# GasALIM.net
KiCad netlist of a schematic drawn in EAGLE
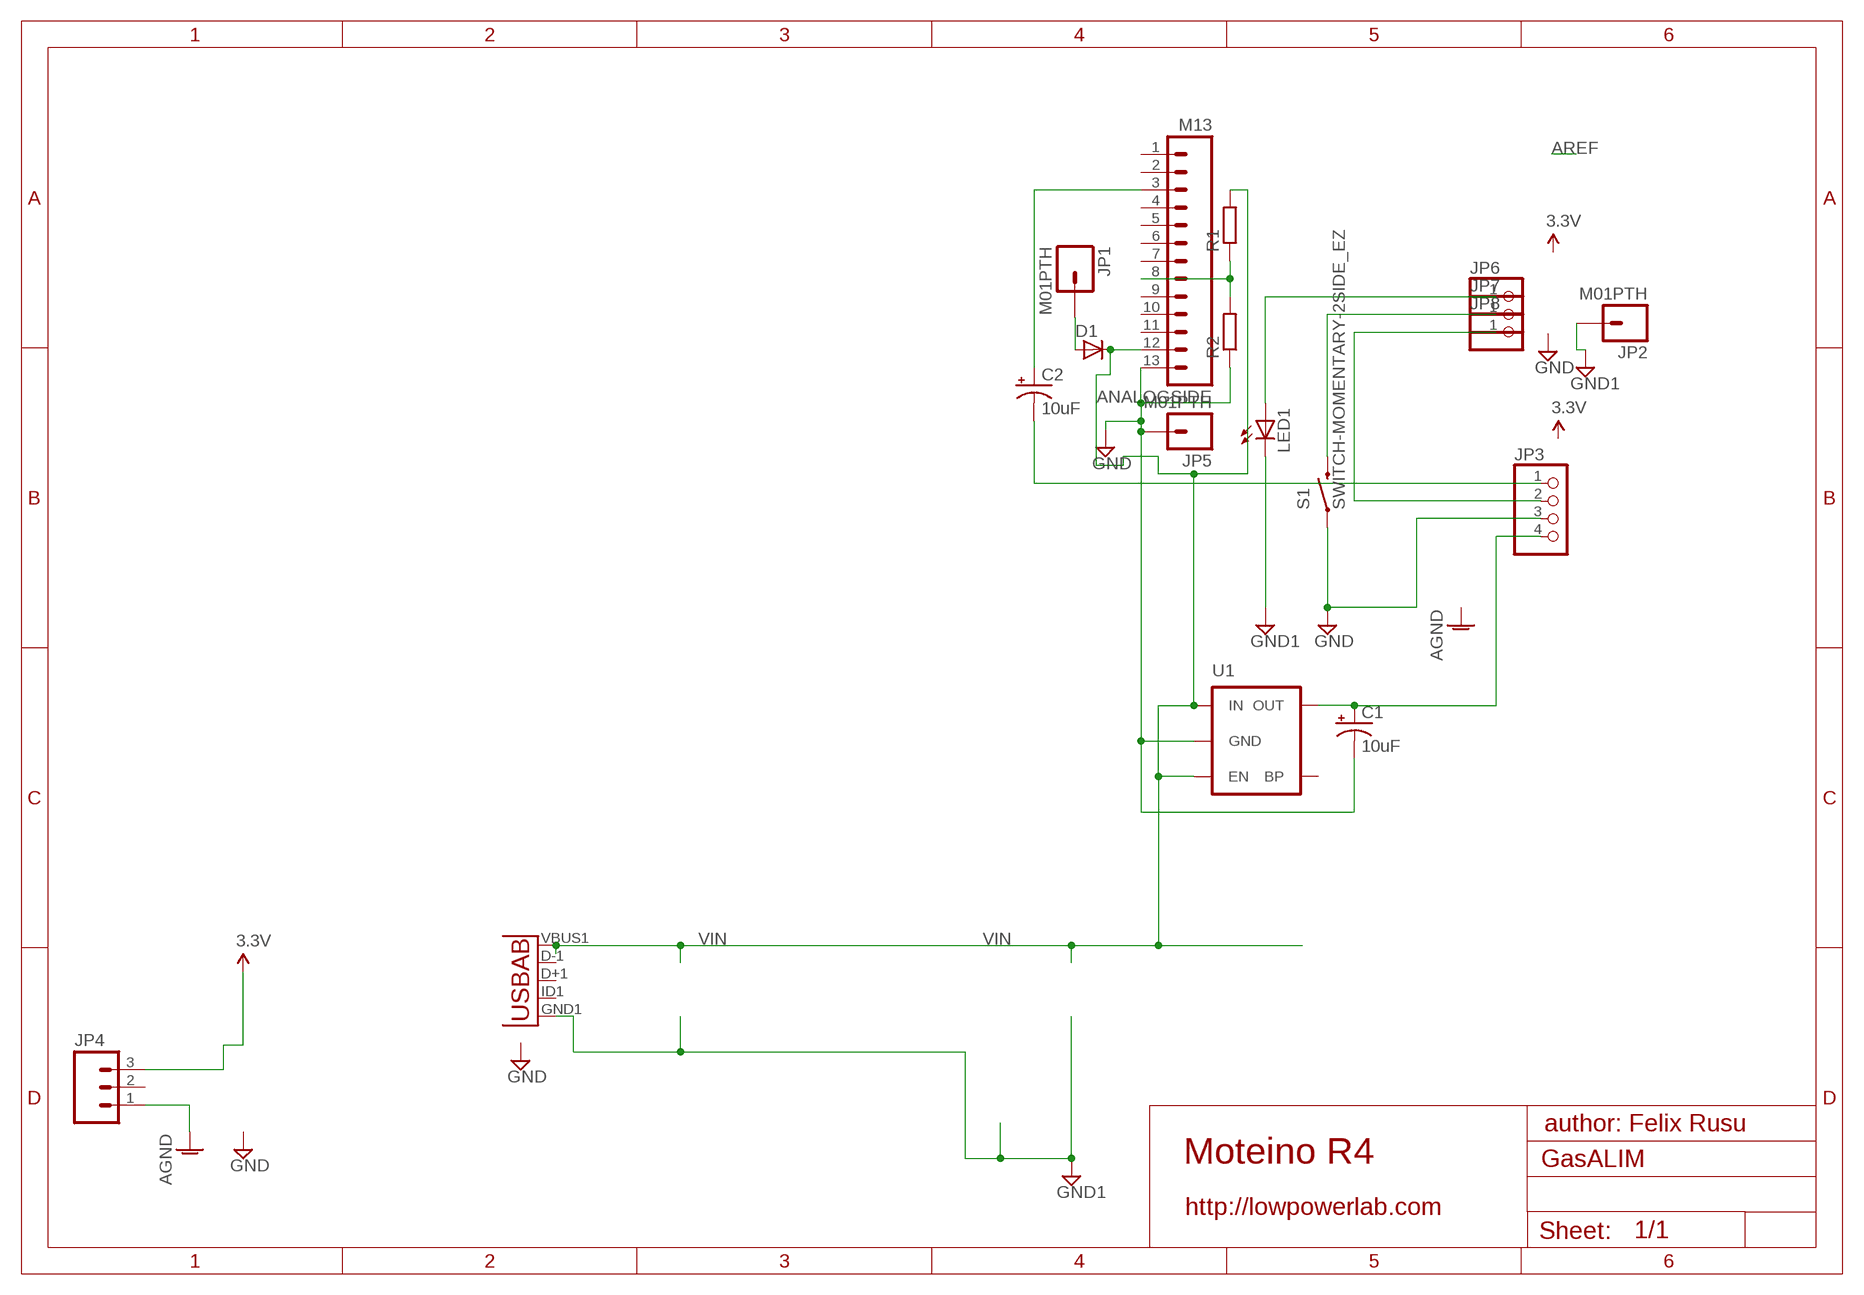
[diagram p0: schematic, sheet 1]

(export (version "E")
  (design (tool "Eeschema 10.0.6"))
  (components
    (comp (ref "ANALOGSIDE")
      (value "M13")
      (footprint "eagle-import:1X13")
      (libsource (lib "eagle-import") (part "M13"))
    )
    (comp (ref "C1")
      (value "10uF")
      (footprint "eagle-import:EIA3216")
      (libsource (lib "eagle-import") (part "10UF-16V-10%(TANT)"))
    )
    (comp (ref "C2")
      (value "10uF")
      (footprint "eagle-import:EIA3216")
      (libsource (lib "eagle-import") (part "10UF-16V-10%(TANT)"))
    )
    (comp (ref "D1")
      (value "D-MLL-34")
      (footprint "eagle-import:MELF-MLL34")
      (libsource (lib "eagle-import") (part "D-MLL-34"))
    )
    (comp (ref "JP1")
      (value "M01PTH")
      (footprint "eagle-import:1X01")
      (libsource (lib "eagle-import") (part "M01PTH"))
    )
    (comp (ref "JP2")
      (value "M01PTH")
      (footprint "eagle-import:1X01")
      (libsource (lib "eagle-import") (part "M01PTH"))
    )
    (comp (ref "JP3")
      (value "PINHD-1X4")
      (footprint "eagle-import:1X04")
      (libsource (lib "eagle-import") (part "PINHD-1X4"))
    )
    (comp (ref "JP4")
      (value "M03PTH")
      (footprint "eagle-import:1X03")
      (libsource (lib "eagle-import") (part "M03PTH"))
    )
    (comp (ref "JP5")
      (value "M01PTH")
      (footprint "eagle-import:1X01")
      (libsource (lib "eagle-import") (part "M01PTH"))
    )
    (comp (ref "JP6")
      (value "PINHD-1X1")
      (footprint "eagle-import:1X01")
      (libsource (lib "eagle-import") (part "PINHD-1X1"))
    )
    (comp (ref "JP7")
      (value "PINHD-1X1")
      (footprint "eagle-import:1X01")
      (libsource (lib "eagle-import") (part "PINHD-1X1"))
    )
    (comp (ref "JP8")
      (value "PINHD-1X1")
      (footprint "eagle-import:1X01")
      (libsource (lib "eagle-import") (part "PINHD-1X1"))
    )
    (comp (ref "JP9")
      (value "Micro USB")
      (footprint "eagle-import:USB-AB-MICRO-SMD_V03")
      (libsource (lib "eagle-import") (part "USB-ABCONN-11794"))
    )
    (comp (ref "LED1")
      (value "LED3MM")
      (footprint "eagle-import:LED3MM")
      (libsource (lib "eagle-import") (part "LED3MM"))
    )
    (comp (ref "R1")
      (value "R-EU_0204/7")
      (footprint "eagle-import:0204_7")
      (libsource (lib "eagle-import") (part "R-EU_0204/7"))
    )
    (comp (ref "R2")
      (value "R-EU_0204/7")
      (footprint "eagle-import:0204_7")
      (libsource (lib "eagle-import") (part "R-EU_0204/7"))
    )
    (comp (ref "S1")
      (value "SWITCH-MOMENTARY-2SIDE_EZ")
      (footprint "eagle-import:TACTILE-PTH-SIDEEZ")
      (libsource (lib "eagle-import") (part "SWITCH-MOMENTARY-2SIDE_EZ"))
    )
    (comp (ref "U1")
      (value "MIC52055V")
      (footprint "eagle-import:SOT23-5@1")
      (libsource (lib "eagle-import") (part "MIC52055V"))
    )
  )
  (nets
    (net (code "2") (name "/VIN") (class "Default")
      (node (ref "ANALOGSIDE") (pin "12") (pinfunction "12_12") (pintype "passive"))
      (node (ref "D1") (pin "1") (pinfunction "C_1") (pintype "passive"))
      (node (ref "JP9") (pin "VBUS1") (pinfunction "VBUS_VBUS1") (pintype "bidirectional"))
      (node (ref "R1") (pin "2") (pinfunction "2_2") (pintype "passive"))
      (node (ref "U1") (pin "1") (pinfunction "IN_1") (pintype "input"))
      (node (ref "U1") (pin "3") (pinfunction "EN_3") (pintype "input"))
    )
    (net (code "3") (name "3.3V") (class "Default")
      (node (ref "JP4") (pin "3") (pinfunction "3_3") (pintype "passive"))
    )
    (net (code "4") (name "AGND") (class "Default")
      (node (ref "JP4") (pin "1") (pinfunction "1_1") (pintype "passive"))
    )
    (net (code "5") (name "GND") (class "Default")
      (node (ref "ANALOGSIDE") (pin "13") (pinfunction "13_13") (pintype "passive"))
      (node (ref "C1") (pin "C") (pinfunction "-_C") (pintype "passive"))
      (node (ref "JP3") (pin "3") (pinfunction "3_3") (pintype "passive"))
      (node (ref "JP5") (pin "1") (pinfunction "1_1") (pintype "passive"))
      (node (ref "R2") (pin "1") (pinfunction "1_1") (pintype "passive"))
      (node (ref "S1") (pin "1") (pinfunction "1_1") (pintype "passive"))
      (node (ref "U1") (pin "2") (pinfunction "GND_2") (pintype "input"))
    )
    (net (code "6") (name "GND1") (class "Default")
      (node (ref "JP2") (pin "1") (pinfunction "1_1") (pintype "passive"))
      (node (ref "JP9") (pin "GND1") (pinfunction "GND_GND1") (pintype "bidirectional"))
      (node (ref "LED1") (pin "K") (pinfunction "C_K") (pintype "passive"))
    )
    (net (code "7") (name "Net-(ANALOGSIDE-Pad8)") (class "Default")
      (node (ref "ANALOGSIDE") (pin "8") (pinfunction "8_8") (pintype "passive"))
      (node (ref "R1") (pin "1") (pinfunction "1_1") (pintype "passive"))
      (node (ref "R2") (pin "2") (pinfunction "2_2") (pintype "passive"))
    )
    (net (code "8") (name "Net-(C1-+)") (class "Default")
      (node (ref "C1") (pin "A") (pinfunction "+_A") (pintype "passive"))
      (node (ref "JP3") (pin "4") (pinfunction "4_4") (pintype "passive"))
      (node (ref "U1") (pin "5") (pinfunction "OUT_5") (pintype "passive"))
    )
    (net (code "9") (name "Net-(C2-+)") (class "Default")
      (node (ref "ANALOGSIDE") (pin "3") (pinfunction "3_3") (pintype "passive"))
      (node (ref "C2") (pin "A") (pinfunction "+_A") (pintype "passive"))
    )
    (net (code "10") (name "Net-(C2--)") (class "Default")
      (node (ref "C2") (pin "C") (pinfunction "-_C") (pintype "passive"))
      (node (ref "JP3") (pin "1") (pinfunction "1_1") (pintype "passive"))
    )
    (net (code "11") (name "Net-(D1-A)") (class "Default")
      (node (ref "D1") (pin "2") (pinfunction "A_2") (pintype "passive"))
      (node (ref "JP1") (pin "1") (pinfunction "1_1") (pintype "passive"))
    )
    (net (code "12") (name "Net-(JP3-Pad2)") (class "Default")
      (node (ref "JP3") (pin "2") (pinfunction "2_2") (pintype "passive"))
      (node (ref "JP8") (pin "1") (pinfunction "1_1") (pintype "passive"))
    )
    (net (code "13") (name "Net-(JP6-Pad1)") (class "Default")
      (node (ref "JP6") (pin "1") (pinfunction "1_1") (pintype "passive"))
      (node (ref "LED1") (pin "A") (pinfunction "A_A") (pintype "passive"))
    )
    (net (code "14") (name "Net-(JP7-Pad1)") (class "Default")
      (node (ref "JP7") (pin "1") (pinfunction "1_1") (pintype "passive"))
      (node (ref "S1") (pin "2") (pinfunction "2_2") (pintype "passive"))
    )
    (net (code "15") (name "unconnected-(ANALOGSIDE-Pad1)") (class "Default")
      (node (ref "ANALOGSIDE") (pin "1") (pinfunction "1_1") (pintype "passive"))
    )
    (net (code "16") (name "unconnected-(ANALOGSIDE-Pad2)") (class "Default")
      (node (ref "ANALOGSIDE") (pin "2") (pinfunction "2_2") (pintype "passive"))
    )
    (net (code "17") (name "unconnected-(ANALOGSIDE-Pad4)") (class "Default")
      (node (ref "ANALOGSIDE") (pin "4") (pinfunction "4_4") (pintype "passive"))
    )
    (net (code "18") (name "unconnected-(ANALOGSIDE-Pad5)") (class "Default")
      (node (ref "ANALOGSIDE") (pin "5") (pinfunction "5_5") (pintype "passive"))
    )
    (net (code "19") (name "unconnected-(ANALOGSIDE-Pad6)") (class "Default")
      (node (ref "ANALOGSIDE") (pin "6") (pinfunction "6_6") (pintype "passive"))
    )
    (net (code "20") (name "unconnected-(ANALOGSIDE-Pad7)") (class "Default")
      (node (ref "ANALOGSIDE") (pin "7") (pinfunction "7_7") (pintype "passive"))
    )
    (net (code "21") (name "unconnected-(ANALOGSIDE-Pad9)") (class "Default")
      (node (ref "ANALOGSIDE") (pin "9") (pinfunction "9_9") (pintype "passive"))
    )
    (net (code "22") (name "unconnected-(ANALOGSIDE-Pad10)") (class "Default")
      (node (ref "ANALOGSIDE") (pin "10") (pinfunction "10_10") (pintype "passive"))
    )
    (net (code "23") (name "unconnected-(ANALOGSIDE-Pad11)") (class "Default")
      (node (ref "ANALOGSIDE") (pin "11") (pinfunction "11_11") (pintype "passive"))
    )
    (net (code "24") (name "unconnected-(JP4-Pad2)") (class "Default")
      (node (ref "JP4") (pin "2") (pinfunction "2_2") (pintype "passive"))
    )
    (net (code "25") (name "unconnected-(JP9-D+-PadD+1)") (class "Default")
      (node (ref "JP9") (pin "D+1") (pinfunction "D+_D+1") (pintype "bidirectional"))
    )
    (net (code "26") (name "unconnected-(JP9-D--PadD-1)") (class "Default")
      (node (ref "JP9") (pin "D-1") (pinfunction "D-_D-1") (pintype "bidirectional"))
    )
    (net (code "27") (name "unconnected-(JP9-USBID-PadID1)") (class "Default")
      (node (ref "JP9") (pin "ID1") (pinfunction "USBID_ID1") (pintype "bidirectional"))
    )
    (net (code "28") (name "unconnected-(U1-BP-Pad4)") (class "Default")
      (node (ref "U1") (pin "4") (pinfunction "BP_4") (pintype "input"))
    )
  )
)
